# ict_v361-xs.net
KiCad netlist of a schematic drawn in EAGLE
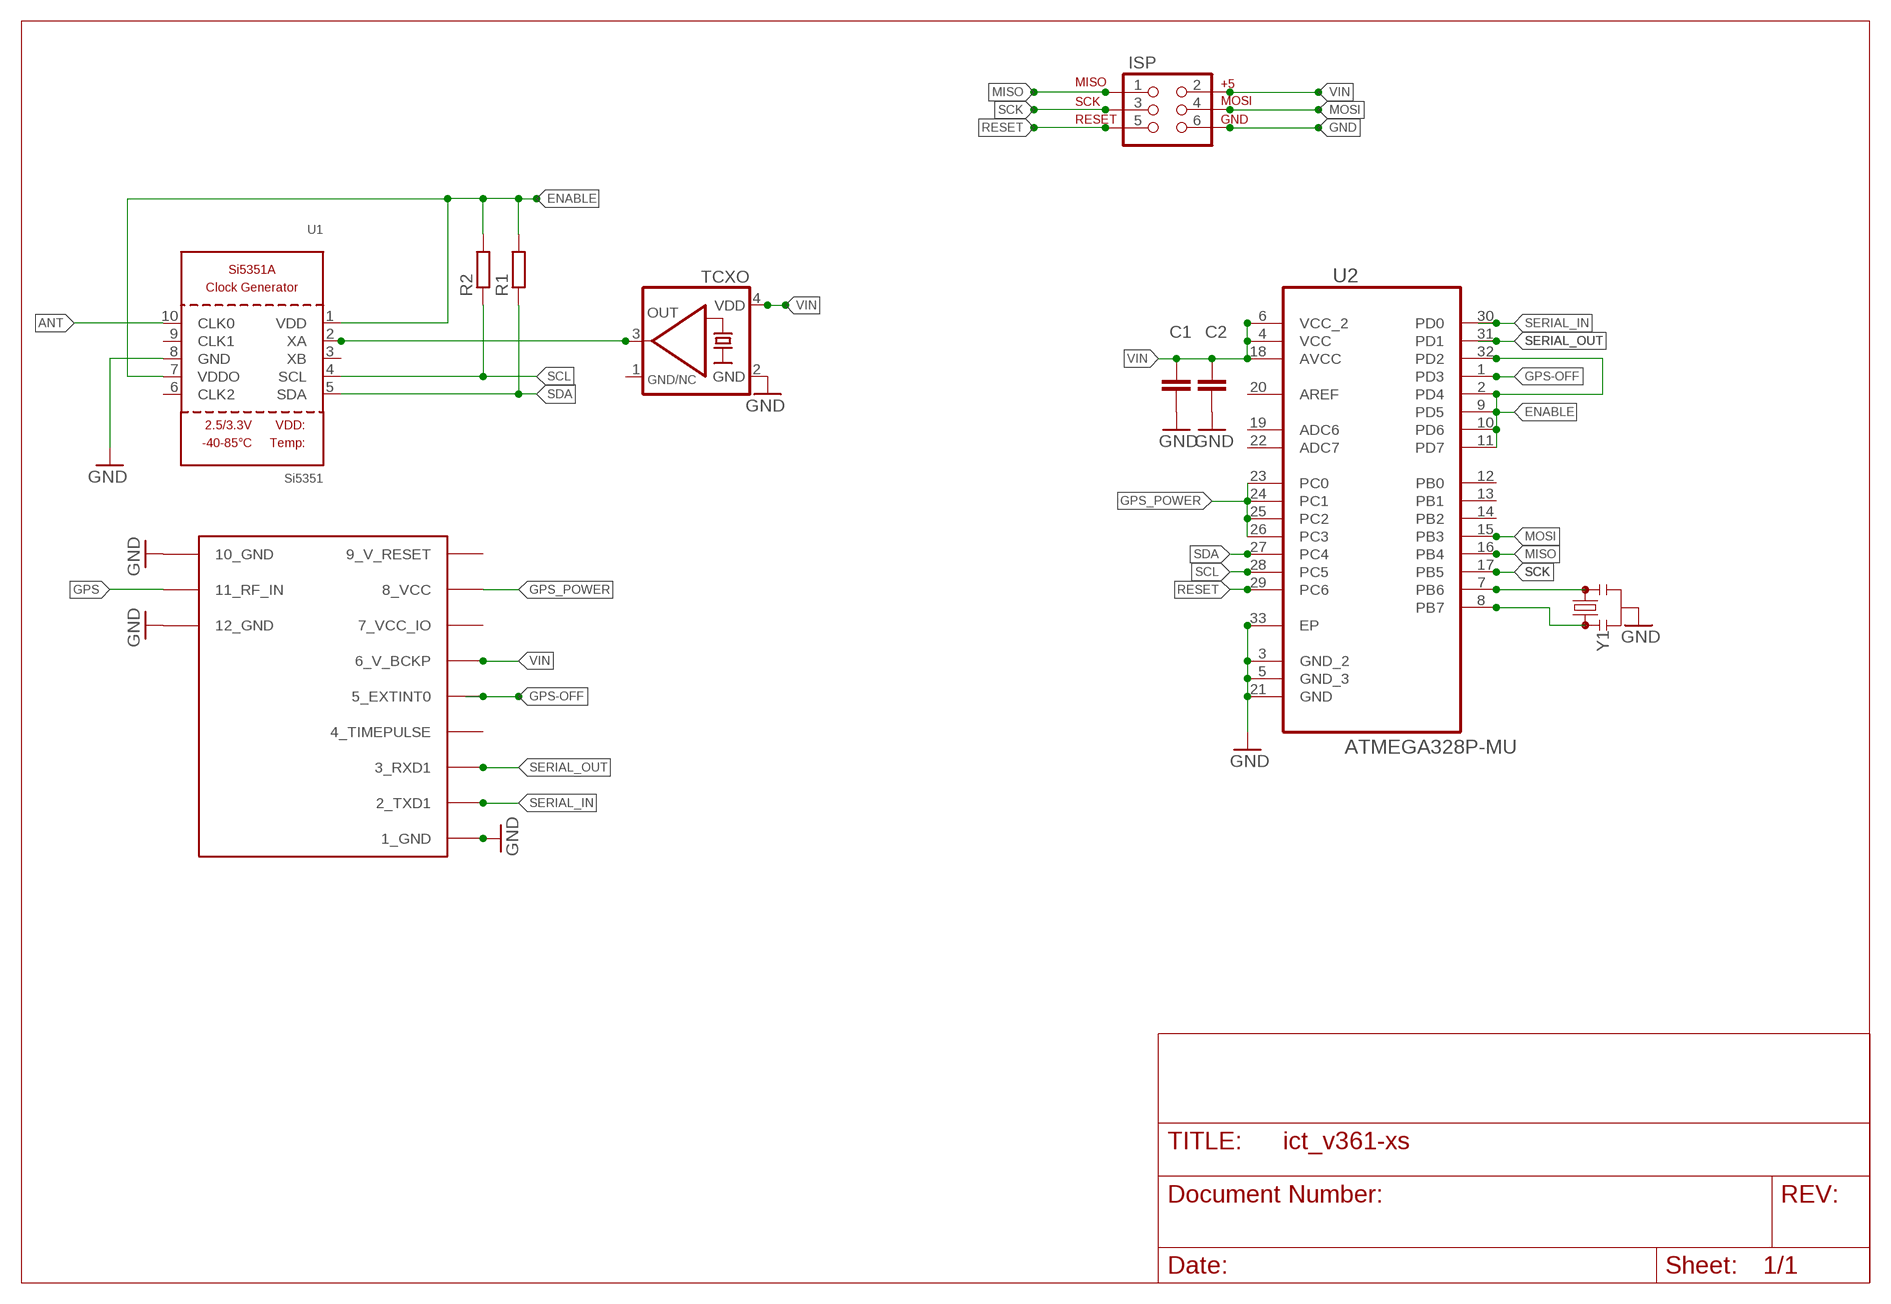
[diagram p0: schematic, sheet 1]

(export (version "E")
  (design (tool "Eeschema 10.0.6"))
  (components
    (comp (ref "C1")
      (value "C-EUC0603K")
      (footprint "eagle-import:C0603K")
      (libsource (lib "eagle-import") (part "C-EUC0603K"))
    )
    (comp (ref "C2")
      (value "C-EUC0603K")
      (footprint "eagle-import:C0603K")
      (libsource (lib "eagle-import") (part "C-EUC0603K"))
    )
    (comp (ref "GPS")
      (value "UBLOX_MAX")
      (footprint "eagle-import:UBLOX_MAX")
      (libsource (lib "eagle-import") (part "UBLOX_MAX"))
    )
    (comp (ref "ISP")
      (value "AVR_SPI_PRG_6PTH")
      (footprint "eagle-import:2X3")
      (libsource (lib "eagle-import") (part "AVR_SPI_PRG_6PTH"))
    )
    (comp (ref "R1")
      (value "R-EU_R0603")
      (footprint "eagle-import:R0603")
      (libsource (lib "eagle-import") (part "R-EU_R0603"))
    )
    (comp (ref "R2")
      (value "R-EU_R0603")
      (footprint "eagle-import:R0603")
      (libsource (lib "eagle-import") (part "R-EU_R0603"))
    )
    (comp (ref "TCXO")
      (value "KXO-TCXO-CMOS-84")
      (footprint "eagle-import:3.2X2.5_KXO-84-TCXO")
      (libsource (lib "eagle-import") (part "KXO-TCXO-CMOS-84"))
    )
    (comp (ref "U1")
      (value "Si5351")
      (footprint "eagle-import:MSOP10")
      (libsource (lib "eagle-import") (part "SI5351A"))
    )
    (comp (ref "U2")
      (value "ATMEGA328P-MU")
      (footprint "eagle-import:QFN50P500X500X100-33N")
      (libsource (lib "eagle-import") (part "ATMEGA328P-MU"))
    )
    (comp (ref "Y1")
      (value "RESONATORSMD-4.5X2.0")
      (footprint "eagle-import:RESONATOR-SMD-4.5X2.0")
      (libsource (lib "eagle-import") (part "RESONATORSMD-4.5X2.0"))
    )
  )
  (nets
    (net (code "1") (name "/7_VCC_IO") (class "Default")
      (node (ref "GPS") (pin "7_VCC_IO") (pinfunction "7_VCC_IO_7_VCC_IO") (pintype "power_in"))
    )
    (net (code "2") (name "/9_V_RESET") (class "Default")
      (node (ref "GPS") (pin "9_V_RESET") (pinfunction "9_V_RESET_9_V_RESET") (pintype "power_in"))
    )
    (net (code "3") (name "/GND{slash}NC") (class "Default")
      (node (ref "TCXO") (pin "1") (pinfunction "GND/NC_1") (pintype "power_in"))
    )
    (net (code "4") (name "ANT") (class "Default")
      (node (ref "U1") (pin "10") (pinfunction "CLK0_10") (pintype "output"))
    )
    (net (code "5") (name "ENABLE") (class "Default")
      (node (ref "R1") (pin "2") (pinfunction "2_2") (pintype "passive"))
      (node (ref "R2") (pin "2") (pinfunction "2_2") (pintype "passive"))
      (node (ref "U1") (pin "1") (pinfunction "VDD_1") (pintype "power_in"))
      (node (ref "U1") (pin "7") (pinfunction "VDDO_7") (pintype "power_in"))
      (node (ref "U2") (pin "10") (pinfunction "PD6_10") (pintype "bidirectional"))
      (node (ref "U2") (pin "11") (pinfunction "PD7_11") (pintype "bidirectional"))
      (node (ref "U2") (pin "2") (pinfunction "PD4_2") (pintype "bidirectional"))
      (node (ref "U2") (pin "32") (pinfunction "PD2_32") (pintype "bidirectional"))
      (node (ref "U2") (pin "9") (pinfunction "PD5_9") (pintype "bidirectional"))
    )
    (net (code "6") (name "GND") (class "Default")
      (node (ref "C1") (pin "2") (pinfunction "2_2") (pintype "passive"))
      (node (ref "C2") (pin "2") (pinfunction "2_2") (pintype "passive"))
      (node (ref "GPS") (pin "10_GND") (pinfunction "10_GND_10_GND") (pintype "power_in"))
      (node (ref "GPS") (pin "12_GND") (pinfunction "12_GND_12_GND") (pintype "power_in"))
      (node (ref "GPS") (pin "1_GND") (pinfunction "1_GND_1_GND") (pintype "power_in"))
      (node (ref "ISP") (pin "6") (pinfunction "6_6") (pintype "passive"))
      (node (ref "TCXO") (pin "2") (pinfunction "GND_2") (pintype "power_in"))
      (node (ref "U1") (pin "8") (pinfunction "GND_8") (pintype "power_in"))
      (node (ref "U2") (pin "21") (pinfunction "GND_21") (pintype "passive"))
      (node (ref "U2") (pin "3") (pinfunction "GND_2_3") (pintype "passive"))
      (node (ref "U2") (pin "33") (pinfunction "EP_33") (pintype "passive"))
      (node (ref "U2") (pin "5") (pinfunction "GND_3_5") (pintype "passive"))
      (node (ref "Y1") (pin "2") (pinfunction "2_2") (pintype "passive"))
    )
    (net (code "7") (name "GPS") (class "Default")
      (node (ref "GPS") (pin "11_RF_IN") (pinfunction "11_RF_IN_11_RF_IN") (pintype "bidirectional"))
    )
    (net (code "8") (name "GPS-OFF") (class "Default")
      (node (ref "GPS") (pin "5_EXTINT0") (pinfunction "5_EXTINT0_5_EXTINT0") (pintype "bidirectional"))
      (node (ref "U2") (pin "1") (pinfunction "PD3_1") (pintype "bidirectional"))
    )
    (net (code "9") (name "GPS_POWER") (class "Default")
      (node (ref "GPS") (pin "8_VCC") (pinfunction "8_VCC_8_VCC") (pintype "power_in"))
      (node (ref "U2") (pin "23") (pinfunction "PC0_23") (pintype "bidirectional"))
      (node (ref "U2") (pin "24") (pinfunction "PC1_24") (pintype "bidirectional"))
      (node (ref "U2") (pin "25") (pinfunction "PC2_25") (pintype "bidirectional"))
      (node (ref "U2") (pin "26") (pinfunction "PC3_26") (pintype "bidirectional"))
    )
    (net (code "10") (name "MISO") (class "Default")
      (node (ref "ISP") (pin "1") (pinfunction "1_1") (pintype "passive"))
      (node (ref "U2") (pin "16") (pinfunction "PB4_16") (pintype "bidirectional"))
    )
    (net (code "11") (name "MOSI") (class "Default")
      (node (ref "ISP") (pin "4") (pinfunction "4_4") (pintype "passive"))
      (node (ref "U2") (pin "15") (pinfunction "PB3_15") (pintype "bidirectional"))
    )
    (net (code "12") (name "Net-(TCXO-OUT)") (class "Default")
      (node (ref "TCXO") (pin "3") (pinfunction "OUT_3") (pintype "output"))
      (node (ref "U1") (pin "2") (pinfunction "XA_2") (pintype "input"))
    )
    (net (code "13") (name "Net-(U2-PB6)") (class "Default")
      (node (ref "U2") (pin "7") (pinfunction "PB6_7") (pintype "bidirectional"))
      (node (ref "Y1") (pin "3") (pinfunction "3_3") (pintype "passive"))
    )
    (net (code "14") (name "Net-(U2-PB7)") (class "Default")
      (node (ref "U2") (pin "8") (pinfunction "PB7_8") (pintype "bidirectional"))
      (node (ref "Y1") (pin "1") (pinfunction "1_1") (pintype "passive"))
    )
    (net (code "15") (name "RESET") (class "Default")
      (node (ref "ISP") (pin "5") (pinfunction "5_5") (pintype "passive"))
      (node (ref "U2") (pin "29") (pinfunction "PC6_29") (pintype "bidirectional"))
    )
    (net (code "16") (name "SCK") (class "Default")
      (node (ref "ISP") (pin "3") (pinfunction "3_3") (pintype "passive"))
      (node (ref "U2") (pin "17") (pinfunction "PB5_17") (pintype "bidirectional"))
    )
    (net (code "17") (name "SCL") (class "Default")
      (node (ref "R2") (pin "1") (pinfunction "1_1") (pintype "passive"))
      (node (ref "U1") (pin "4") (pinfunction "SCL_4") (pintype "input"))
      (node (ref "U2") (pin "28") (pinfunction "PC5_28") (pintype "bidirectional"))
    )
    (net (code "18") (name "SDA") (class "Default")
      (node (ref "R1") (pin "1") (pinfunction "1_1") (pintype "passive"))
      (node (ref "U1") (pin "5") (pinfunction "SDA_5") (pintype "bidirectional"))
      (node (ref "U2") (pin "27") (pinfunction "PC4_27") (pintype "bidirectional"))
    )
    (net (code "19") (name "SERIAL_IN") (class "Default")
      (node (ref "GPS") (pin "2_TXD1") (pinfunction "2_TXD1_2_TXD1") (pintype "bidirectional"))
      (node (ref "U2") (pin "30") (pinfunction "PD0_30") (pintype "bidirectional"))
    )
    (net (code "20") (name "SERIAL_OUT") (class "Default")
      (node (ref "GPS") (pin "3_RXD1") (pinfunction "3_RXD1_3_RXD1") (pintype "bidirectional"))
      (node (ref "U2") (pin "31") (pinfunction "PD1_31") (pintype "bidirectional"))
    )
    (net (code "21") (name "VIN") (class "Default")
      (node (ref "C1") (pin "1") (pinfunction "1_1") (pintype "passive"))
      (node (ref "C2") (pin "1") (pinfunction "1_1") (pintype "passive"))
      (node (ref "GPS") (pin "6_V_BCKP") (pinfunction "6_V_BCKP_6_V_BCKP") (pintype "bidirectional"))
      (node (ref "ISP") (pin "2") (pinfunction "2_2") (pintype "passive"))
      (node (ref "TCXO") (pin "4") (pinfunction "VDD_4") (pintype "power_in"))
      (node (ref "U2") (pin "18") (pinfunction "AVCC_18") (pintype "power_in"))
      (node (ref "U2") (pin "4") (pinfunction "VCC_4") (pintype "power_in"))
      (node (ref "U2") (pin "6") (pinfunction "VCC_2_6") (pintype "power_in"))
    )
    (net (code "22") (name "unconnected-(GPS-Pad4_TIMEPULSE)") (class "Default")
      (node (ref "GPS") (pin "4_TIMEPULSE") (pinfunction "4_TIMEPULSE_4_TIMEPULSE") (pintype "bidirectional"))
    )
    (net (code "23") (name "unconnected-(U1-CLK1-Pad9)") (class "Default")
      (node (ref "U1") (pin "9") (pinfunction "CLK1_9") (pintype "output"))
    )
    (net (code "24") (name "unconnected-(U1-CLK2-Pad6)") (class "Default")
      (node (ref "U1") (pin "6") (pinfunction "CLK2_6") (pintype "output"))
    )
    (net (code "25") (name "unconnected-(U1-XB-Pad3)") (class "Default")
      (node (ref "U1") (pin "3") (pinfunction "XB_3") (pintype "input"))
    )
    (net (code "26") (name "unconnected-(U2-ADC6-Pad19)") (class "Default")
      (node (ref "U2") (pin "19") (pinfunction "ADC6_19") (pintype "input"))
    )
    (net (code "27") (name "unconnected-(U2-ADC7-Pad22)") (class "Default")
      (node (ref "U2") (pin "22") (pinfunction "ADC7_22") (pintype "input"))
    )
    (net (code "28") (name "unconnected-(U2-AREF-Pad20)") (class "Default")
      (node (ref "U2") (pin "20") (pinfunction "AREF_20") (pintype "input"))
    )
    (net (code "29") (name "unconnected-(U2-PB0-Pad12)") (class "Default")
      (node (ref "U2") (pin "12") (pinfunction "PB0_12") (pintype "bidirectional"))
    )
    (net (code "30") (name "unconnected-(U2-PB1-Pad13)") (class "Default")
      (node (ref "U2") (pin "13") (pinfunction "PB1_13") (pintype "bidirectional"))
    )
    (net (code "31") (name "unconnected-(U2-PB2-Pad14)") (class "Default")
      (node (ref "U2") (pin "14") (pinfunction "PB2_14") (pintype "bidirectional"))
    )
  )
)
